# homedunio.net
KiCad netlist of a schematic drawn in EAGLE
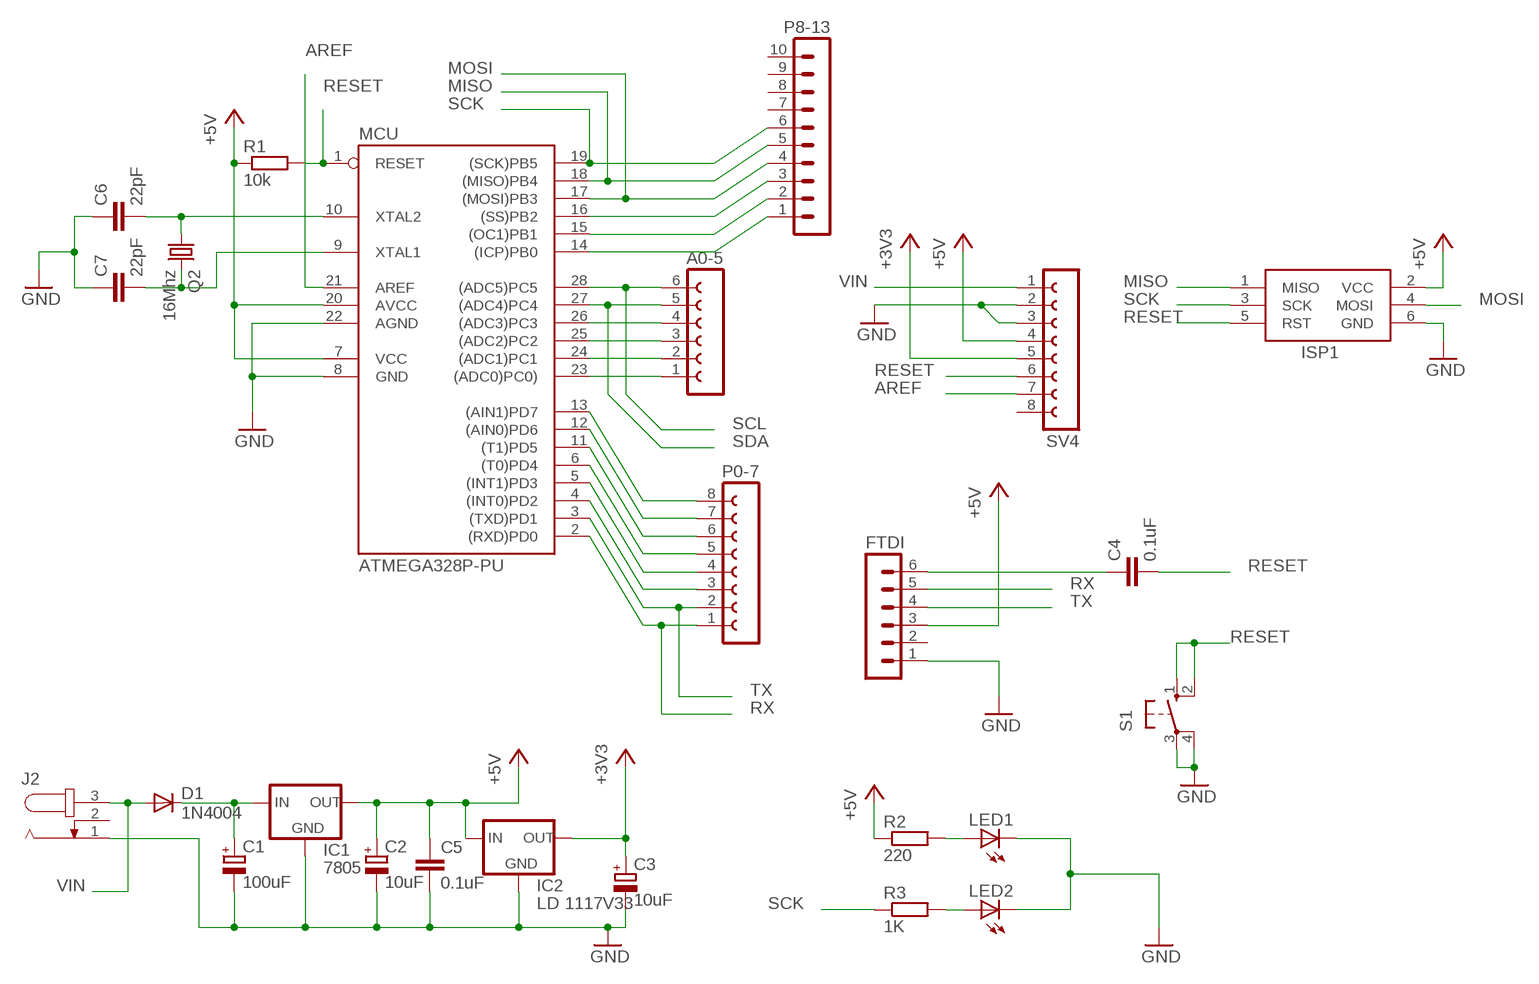
[diagram p0: schematic, sheet 1]

(export (version "E")
  (design (tool "Eeschema 10.0.6"))
  (components
    (comp (ref "A0-5")
      (value "FE06-1")
      (footprint "eagle-import:FE06")
      (libsource (lib "eagle-import") (part "FE06-1"))
    )
    (comp (ref "C1")
      (value "100uF")
      (footprint "eagle-import:E2,5-5")
      (libsource (lib "eagle-import") (part "CPOL-EUE2.5-5"))
    )
    (comp (ref "C2")
      (value "10uF")
      (footprint "eagle-import:E2,5-5")
      (libsource (lib "eagle-import") (part "CPOL-EUE2.5-5"))
    )
    (comp (ref "C3")
      (value "10uF")
      (footprint "eagle-import:E2,5-5")
      (libsource (lib "eagle-import") (part "CPOL-EUE2.5-5"))
    )
    (comp (ref "C4")
      (value "0.1uF")
      (footprint "eagle-import:C025-060X050")
      (libsource (lib "eagle-import") (part "C-EU025-060X050"))
    )
    (comp (ref "C5")
      (value "0.1uF")
      (footprint "eagle-import:C025-060X050")
      (libsource (lib "eagle-import") (part "C-EU025-060X050"))
    )
    (comp (ref "C6")
      (value "22pF")
      (footprint "eagle-import:C025-060X050")
      (libsource (lib "eagle-import") (part "C-EU025-060X050"))
    )
    (comp (ref "C7")
      (value "22pF")
      (footprint "eagle-import:C025-060X050")
      (libsource (lib "eagle-import") (part "C-EU025-060X050"))
    )
    (comp (ref "D1")
      (value "1N4004")
      (footprint "eagle-import:DO41-10")
      (libsource (lib "eagle-import") (part "1N4004"))
    )
    (comp (ref "FTDI")
      (value "MA06-1")
      (footprint "eagle-import:MA06-1")
      (libsource (lib "eagle-import") (part "MA06-1"))
    )
    (comp (ref "IC1")
      (value "7805")
      (footprint "eagle-import:78XXL")
      (libsource (lib "eagle-import") (part "78XXL"))
    )
    (comp (ref "IC2")
      (value "LD 1117V33")
      (footprint "eagle-import:78XXL")
      (libsource (lib "eagle-import") (part "78XXL"))
    )
    (comp (ref "ISP1")
      (value "AVRISP-6")
      (footprint "eagle-import:AVRISP")
      (libsource (lib "eagle-import") (part "AVRISP-6"))
    )
    (comp (ref "J2")
      (value "JACK-PLUG0")
      (footprint "eagle-import:SPC4077")
      (libsource (lib "eagle-import") (part "JACK-PLUG0"))
    )
    (comp (ref "LED1")
      (value "LED3MM")
      (footprint "eagle-import:LED3MM")
      (libsource (lib "eagle-import") (part "LED3MM"))
    )
    (comp (ref "LED2")
      (value "LED3MM")
      (footprint "eagle-import:LED3MM")
      (libsource (lib "eagle-import") (part "LED3MM"))
    )
    (comp (ref "MCU")
      (value "ATMEGA328P-PU")
      (footprint "eagle-import:DIL28-3")
      (libsource (lib "eagle-import") (part "ATMEGA328P-PU"))
    )
    (comp (ref "P0-7")
      (value "FE08-1")
      (footprint "eagle-import:FE08")
      (libsource (lib "eagle-import") (part "FE08-1"))
    )
    (comp (ref "P8-13")
      (value "MA10-1")
      (footprint "eagle-import:MA10-1")
      (libsource (lib "eagle-import") (part "MA10-1"))
    )
    (comp (ref "Q2")
      (value "16Mhz")
      (footprint "eagle-import:HC49_S")
      (libsource (lib "eagle-import") (part "CRYSTALHC49S"))
    )
    (comp (ref "R1")
      (value "10k")
      (footprint "eagle-import:0204_7")
      (libsource (lib "eagle-import") (part "R-EU_0204/7"))
    )
    (comp (ref "R2")
      (value "220")
      (footprint "eagle-import:0204_7")
      (libsource (lib "eagle-import") (part "R-EU_0204/7"))
    )
    (comp (ref "R3")
      (value "1K")
      (footprint "eagle-import:0204_7")
      (libsource (lib "eagle-import") (part "R-EU_0204/7"))
    )
    (comp (ref "S1")
      (value "10-XX")
      (footprint "eagle-import:B3F-10XX")
      (fields (field (name "MPN") "B3F-1000"))
      (libsource (lib "eagle-import") (part "10-XX"))
    )
    (comp (ref "SV4")
      (value "FE08-1")
      (footprint "eagle-import:FE08")
      (libsource (lib "eagle-import") (part "FE08-1"))
    )
  )
  (nets
    (net (code "1") (name "+3V3") (class "Default")
      (node (ref "C3") (pin "+") (pinfunction "+_+") (pintype "passive"))
      (node (ref "IC2") (pin "OUT") (pinfunction "OUT_OUT") (pintype "passive"))
      (node (ref "SV4") (pin "5") (pinfunction "5_5") (pintype "passive"))
    )
    (net (code "2") (name "+5V") (class "Default")
      (node (ref "C2") (pin "+") (pinfunction "+_+") (pintype "passive"))
      (node (ref "C5") (pin "1") (pinfunction "1_1") (pintype "passive"))
      (node (ref "FTDI") (pin "3") (pinfunction "3_3") (pintype "passive"))
      (node (ref "IC1") (pin "OUT") (pinfunction "OUT_OUT") (pintype "passive"))
      (node (ref "IC2") (pin "IN") (pinfunction "IN_IN") (pintype "input"))
      (node (ref "ISP1") (pin "2") (pinfunction "VCC_2") (pintype "power_in"))
      (node (ref "MCU") (pin "20") (pinfunction "AVCC_20") (pintype "power_in"))
      (node (ref "MCU") (pin "7") (pinfunction "VCC_7") (pintype "power_in"))
      (node (ref "R1") (pin "1") (pinfunction "1_1") (pintype "passive"))
      (node (ref "R2") (pin "1") (pinfunction "1_1") (pintype "passive"))
      (node (ref "SV4") (pin "4") (pinfunction "4_4") (pintype "passive"))
    )
    (net (code "3") (name "/AREF") (class "Default")
      (node (ref "MCU") (pin "21") (pinfunction "AREF_21") (pintype "passive"))
      (node (ref "SV4") (pin "7") (pinfunction "7_7") (pintype "passive"))
    )
    (net (code "4") (name "/MISO") (class "Default")
      (node (ref "ISP1") (pin "1") (pinfunction "MISO_1") (pintype "input"))
      (node (ref "MCU") (pin "18") (pinfunction "(MISO)PB4_18") (pintype "bidirectional"))
      (node (ref "P8-13") (pin "5") (pinfunction "5_5") (pintype "passive"))
    )
    (net (code "5") (name "/MOSI") (class "Default")
      (node (ref "ISP1") (pin "4") (pinfunction "MOSI_4") (pintype "output"))
      (node (ref "MCU") (pin "17") (pinfunction "(MOSI)PB3_17") (pintype "bidirectional"))
      (node (ref "P8-13") (pin "4") (pinfunction "4_4") (pintype "passive"))
    )
    (net (code "6") (name "/RESET") (class "Default")
      (node (ref "C4") (pin "2") (pinfunction "2_2") (pintype "passive"))
      (node (ref "ISP1") (pin "5") (pinfunction "RST_5") (pintype "output"))
      (node (ref "MCU") (pin "1") (pinfunction "RESET_1") (pintype "input"))
      (node (ref "R1") (pin "2") (pinfunction "2_2") (pintype "passive"))
      (node (ref "S1") (pin "1") (pinfunction "S_1") (pintype "passive"))
      (node (ref "S1") (pin "2") (pinfunction "S1_2") (pintype "passive"))
      (node (ref "SV4") (pin "6") (pinfunction "6_6") (pintype "passive"))
    )
    (net (code "7") (name "/RX") (class "Default")
      (node (ref "FTDI") (pin "5") (pinfunction "5_5") (pintype "passive"))
      (node (ref "MCU") (pin "2") (pinfunction "(RXD)PD0_2") (pintype "bidirectional"))
      (node (ref "P0-7") (pin "1") (pinfunction "1_1") (pintype "passive"))
    )
    (net (code "8") (name "/SCK") (class "Default")
      (node (ref "ISP1") (pin "3") (pinfunction "SCK_3") (pintype "output"))
      (node (ref "MCU") (pin "19") (pinfunction "(SCK)PB5_19") (pintype "bidirectional"))
      (node (ref "P8-13") (pin "6") (pinfunction "6_6") (pintype "passive"))
      (node (ref "R3") (pin "1") (pinfunction "1_1") (pintype "passive"))
    )
    (net (code "9") (name "/SCL") (class "Default")
      (node (ref "A0-5") (pin "6") (pinfunction "6_6") (pintype "passive"))
      (node (ref "MCU") (pin "28") (pinfunction "(ADC5)PC5_28") (pintype "bidirectional"))
    )
    (net (code "10") (name "/SDA") (class "Default")
      (node (ref "A0-5") (pin "5") (pinfunction "5_5") (pintype "passive"))
      (node (ref "MCU") (pin "27") (pinfunction "(ADC4)PC4_27") (pintype "bidirectional"))
    )
    (net (code "11") (name "/TX") (class "Default")
      (node (ref "FTDI") (pin "4") (pinfunction "4_4") (pintype "passive"))
      (node (ref "MCU") (pin "3") (pinfunction "(TXD)PD1_3") (pintype "bidirectional"))
      (node (ref "P0-7") (pin "2") (pinfunction "2_2") (pintype "passive"))
    )
    (net (code "12") (name "/VIN") (class "Default")
      (node (ref "D1") (pin "A") (pinfunction "A_A") (pintype "passive"))
      (node (ref "J2") (pin "3") (pinfunction "3_3") (pintype "passive"))
      (node (ref "SV4") (pin "1") (pinfunction "1_1") (pintype "passive"))
    )
    (net (code "13") (name "GND") (class "Default")
      (node (ref "C1") (pin "-") (pinfunction "-_-") (pintype "passive"))
      (node (ref "C2") (pin "-") (pinfunction "-_-") (pintype "passive"))
      (node (ref "C3") (pin "-") (pinfunction "-_-") (pintype "passive"))
      (node (ref "C5") (pin "2") (pinfunction "2_2") (pintype "passive"))
      (node (ref "C6") (pin "1") (pinfunction "1_1") (pintype "passive"))
      (node (ref "C7") (pin "1") (pinfunction "1_1") (pintype "passive"))
      (node (ref "FTDI") (pin "1") (pinfunction "1_1") (pintype "passive"))
      (node (ref "IC1") (pin "GND") (pinfunction "GND_GND") (pintype "input"))
      (node (ref "IC2") (pin "GND") (pinfunction "GND_GND") (pintype "input"))
      (node (ref "ISP1") (pin "6") (pinfunction "GND_6") (pintype "power_in"))
      (node (ref "J2") (pin "1") (pinfunction "1_1") (pintype "passive"))
      (node (ref "LED1") (pin "K") (pinfunction "C_K") (pintype "passive"))
      (node (ref "LED2") (pin "K") (pinfunction "C_K") (pintype "passive"))
      (node (ref "MCU") (pin "22") (pinfunction "AGND_22") (pintype "power_in"))
      (node (ref "MCU") (pin "8") (pinfunction "GND_8") (pintype "power_in"))
      (node (ref "S1") (pin "3") (pinfunction "P_3") (pintype "passive"))
      (node (ref "S1") (pin "4") (pinfunction "P1_4") (pintype "passive"))
      (node (ref "SV4") (pin "2") (pinfunction "2_2") (pintype "passive"))
      (node (ref "SV4") (pin "3") (pinfunction "3_3") (pintype "passive"))
    )
    (net (code "14") (name "Net-(C1-Pad+)") (class "Default")
      (node (ref "C1") (pin "+") (pinfunction "+_+") (pintype "passive"))
      (node (ref "D1") (pin "C") (pinfunction "C_C") (pintype "passive"))
      (node (ref "IC1") (pin "IN") (pinfunction "IN_IN") (pintype "input"))
    )
    (net (code "15") (name "Net-(C4-Pad1)") (class "Default")
      (node (ref "C4") (pin "1") (pinfunction "1_1") (pintype "passive"))
      (node (ref "FTDI") (pin "6") (pinfunction "6_6") (pintype "passive"))
    )
    (net (code "16") (name "Net-(LED1-PadA)") (class "Default")
      (node (ref "LED1") (pin "A") (pinfunction "A_A") (pintype "passive"))
      (node (ref "R2") (pin "2") (pinfunction "2_2") (pintype "passive"))
    )
    (net (code "17") (name "Net-(LED2-PadA)") (class "Default")
      (node (ref "LED2") (pin "A") (pinfunction "A_A") (pintype "passive"))
      (node (ref "R3") (pin "2") (pinfunction "2_2") (pintype "passive"))
    )
    (net (code "18") (name "Net-(MCU-(ADC0)PC0))") (class "Default")
      (node (ref "A0-5") (pin "1") (pinfunction "1_1") (pintype "passive"))
      (node (ref "MCU") (pin "23") (pinfunction "(ADC0)PC0)_23") (pintype "bidirectional"))
    )
    (net (code "19") (name "Net-(MCU-(ADC1)PC1)") (class "Default")
      (node (ref "A0-5") (pin "2") (pinfunction "2_2") (pintype "passive"))
      (node (ref "MCU") (pin "24") (pinfunction "(ADC1)PC1_24") (pintype "bidirectional"))
    )
    (net (code "20") (name "Net-(MCU-(ADC2)PC2)") (class "Default")
      (node (ref "A0-5") (pin "3") (pinfunction "3_3") (pintype "passive"))
      (node (ref "MCU") (pin "25") (pinfunction "(ADC2)PC2_25") (pintype "bidirectional"))
    )
    (net (code "21") (name "Net-(MCU-(ADC3)PC3)") (class "Default")
      (node (ref "A0-5") (pin "4") (pinfunction "4_4") (pintype "passive"))
      (node (ref "MCU") (pin "26") (pinfunction "(ADC3)PC3_26") (pintype "bidirectional"))
    )
    (net (code "22") (name "Net-(MCU-(AIN0)PD6)") (class "Default")
      (node (ref "MCU") (pin "12") (pinfunction "(AIN0)PD6_12") (pintype "bidirectional"))
      (node (ref "P0-7") (pin "7") (pinfunction "7_7") (pintype "passive"))
    )
    (net (code "23") (name "Net-(MCU-(AIN1)PD7)") (class "Default")
      (node (ref "MCU") (pin "13") (pinfunction "(AIN1)PD7_13") (pintype "bidirectional"))
      (node (ref "P0-7") (pin "8") (pinfunction "8_8") (pintype "passive"))
    )
    (net (code "24") (name "Net-(MCU-(ICP)PB0)") (class "Default")
      (node (ref "MCU") (pin "14") (pinfunction "(ICP)PB0_14") (pintype "bidirectional"))
      (node (ref "P8-13") (pin "1") (pinfunction "1_1") (pintype "passive"))
    )
    (net (code "25") (name "Net-(MCU-(INT0)PD2)") (class "Default")
      (node (ref "MCU") (pin "4") (pinfunction "(INT0)PD2_4") (pintype "bidirectional"))
      (node (ref "P0-7") (pin "3") (pinfunction "3_3") (pintype "passive"))
    )
    (net (code "26") (name "Net-(MCU-(INT1)PD3)") (class "Default")
      (node (ref "MCU") (pin "5") (pinfunction "(INT1)PD3_5") (pintype "bidirectional"))
      (node (ref "P0-7") (pin "4") (pinfunction "4_4") (pintype "passive"))
    )
    (net (code "27") (name "Net-(MCU-(OC1)PB1)") (class "Default")
      (node (ref "MCU") (pin "15") (pinfunction "(OC1)PB1_15") (pintype "bidirectional"))
      (node (ref "P8-13") (pin "2") (pinfunction "2_2") (pintype "passive"))
    )
    (net (code "28") (name "Net-(MCU-(SS)PB2)") (class "Default")
      (node (ref "MCU") (pin "16") (pinfunction "(SS)PB2_16") (pintype "bidirectional"))
      (node (ref "P8-13") (pin "3") (pinfunction "3_3") (pintype "passive"))
    )
    (net (code "29") (name "Net-(MCU-(T0)PD4)") (class "Default")
      (node (ref "MCU") (pin "6") (pinfunction "(T0)PD4_6") (pintype "bidirectional"))
      (node (ref "P0-7") (pin "5") (pinfunction "5_5") (pintype "passive"))
    )
    (net (code "30") (name "Net-(MCU-(T1)PD5)") (class "Default")
      (node (ref "MCU") (pin "11") (pinfunction "(T1)PD5_11") (pintype "bidirectional"))
      (node (ref "P0-7") (pin "6") (pinfunction "6_6") (pintype "passive"))
    )
    (net (code "31") (name "Net-(MCU-XTAL1)") (class "Default")
      (node (ref "C7") (pin "2") (pinfunction "2_2") (pintype "passive"))
      (node (ref "MCU") (pin "9") (pinfunction "XTAL1_9") (pintype "bidirectional"))
      (node (ref "Q2") (pin "2") (pinfunction "2_2") (pintype "passive"))
    )
    (net (code "32") (name "Net-(MCU-XTAL2)") (class "Default")
      (node (ref "C6") (pin "2") (pinfunction "2_2") (pintype "passive"))
      (node (ref "MCU") (pin "10") (pinfunction "XTAL2_10") (pintype "bidirectional"))
      (node (ref "Q2") (pin "1") (pinfunction "1_1") (pintype "passive"))
    )
    (net (code "33") (name "unconnected-(FTDI-Pad2)") (class "Default")
      (node (ref "FTDI") (pin "2") (pinfunction "2_2") (pintype "passive"))
    )
    (net (code "34") (name "unconnected-(J2-Pad2)") (class "Default")
      (node (ref "J2") (pin "2") (pinfunction "2_2") (pintype "passive"))
    )
    (net (code "35") (name "unconnected-(P8-13-Pad7)") (class "Default")
      (node (ref "P8-13") (pin "7") (pinfunction "7_7") (pintype "passive"))
    )
    (net (code "36") (name "unconnected-(P8-13-Pad8)") (class "Default")
      (node (ref "P8-13") (pin "8") (pinfunction "8_8") (pintype "passive"))
    )
    (net (code "37") (name "unconnected-(P8-13-Pad9)") (class "Default")
      (node (ref "P8-13") (pin "9") (pinfunction "9_9") (pintype "passive"))
    )
    (net (code "38") (name "unconnected-(P8-13-Pad10)") (class "Default")
      (node (ref "P8-13") (pin "10") (pinfunction "10_10") (pintype "passive"))
    )
    (net (code "39") (name "unconnected-(SV4-Pad8)") (class "Default")
      (node (ref "SV4") (pin "8") (pinfunction "8_8") (pintype "passive"))
    )
  )
)
